# PSU_VCC1V5_Buck.net
KiCad netlist of a schematic drawn in Altium Designer
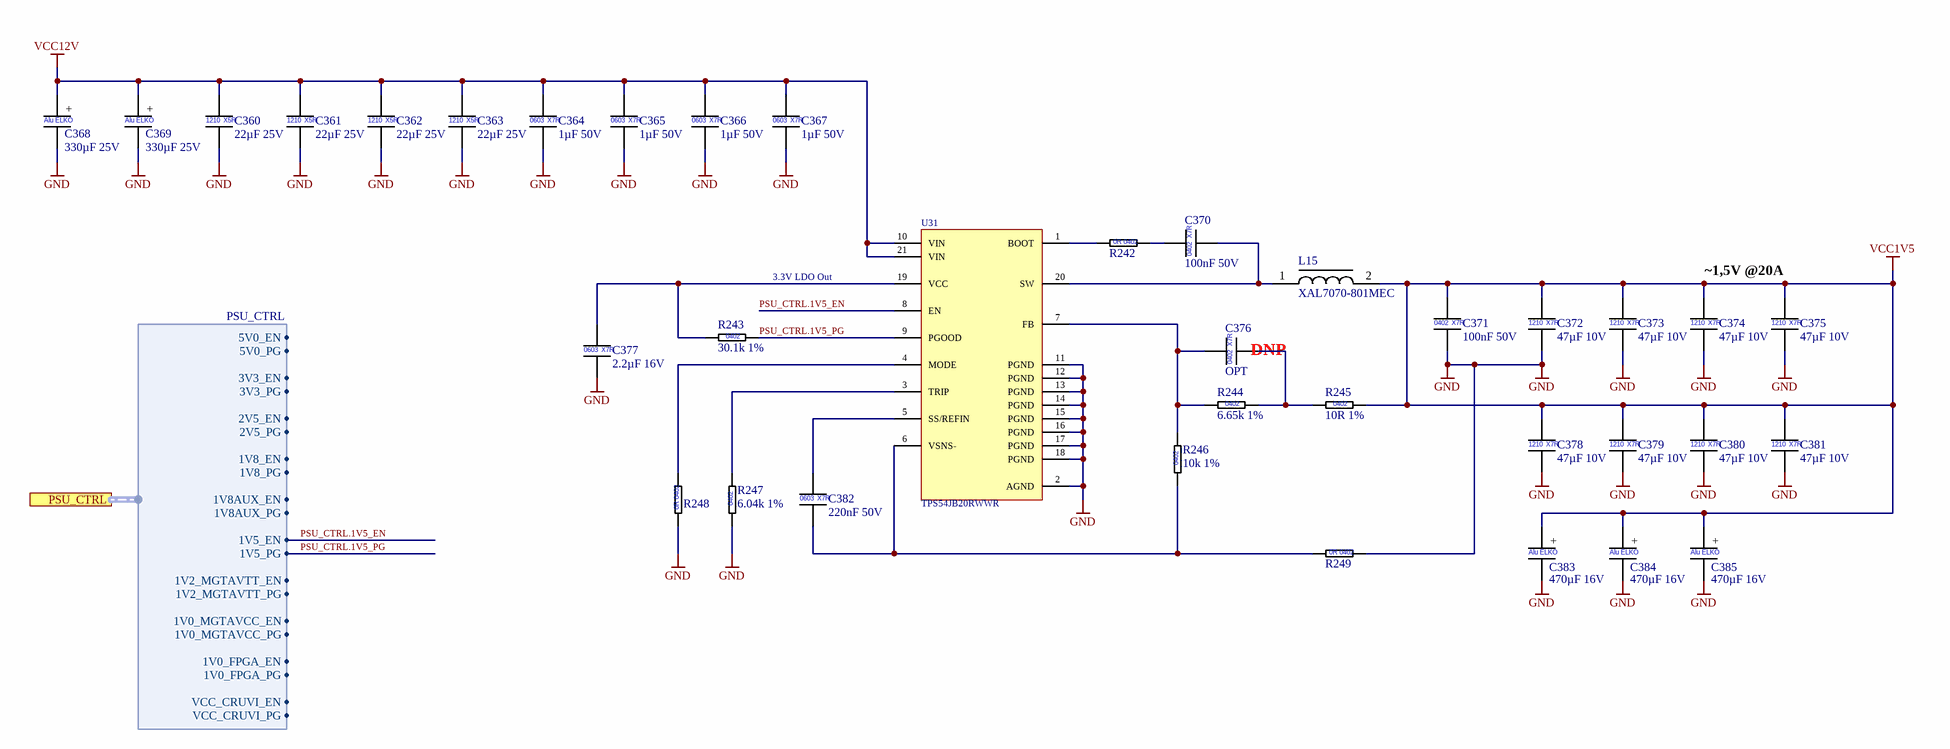
[diagram p0: PSU_VCC1V5_Buck.SchDoc]

(export (version "E")
  (design (tool "Eeschema 10.0.6"))
  (components
    (comp (ref "C360")
      (value "22µF 25V")
      (footprint "Cap:CAP_1210")
      (description "Multilayer Ceramic Capacitors MLCC - SMD/SMT 1210 25VDC")
      (libsource (lib "Cap") (part "CAP_1210_22µF_25V"))
    )
    (comp (ref "C361")
      (value "22µF 25V")
      (footprint "Cap:CAP_1210")
      (description "Multilayer Ceramic Capacitors MLCC - SMD/SMT 1210 25VDC")
      (libsource (lib "Cap") (part "CAP_1210_22µF_25V"))
    )
    (comp (ref "C362")
      (value "22µF 25V")
      (footprint "Cap:CAP_1210")
      (description "Multilayer Ceramic Capacitors MLCC - SMD/SMT 1210 25VDC")
      (libsource (lib "Cap") (part "CAP_1210_22µF_25V"))
    )
    (comp (ref "C363")
      (value "22µF 25V")
      (footprint "Cap:CAP_1210")
      (description "Multilayer Ceramic Capacitors MLCC - SMD/SMT 1210 25VDC")
      (libsource (lib "Cap") (part "CAP_1210_22µF_25V"))
    )
    (comp (ref "C364")
      (value "1µF 50V")
      (footprint "CAP_0603")
      (description "Multilayer Ceramic Capacitors MLCC - SMD/SMT 50V 1uF X7R 0603 10%")
      (libsource (lib "Cap") (part "CAP_0603_1µF_50V_X7R_10%"))
    )
    (comp (ref "C365")
      (value "1µF 50V")
      (footprint "CAP_0603")
      (description "Multilayer Ceramic Capacitors MLCC - SMD/SMT 50V 1uF X7R 0603 10%")
      (libsource (lib "Cap") (part "CAP_0603_1µF_50V_X7R_10%"))
    )
    (comp (ref "C366")
      (value "1µF 50V")
      (footprint "CAP_0603")
      (description "Multilayer Ceramic Capacitors MLCC - SMD/SMT 50V 1uF X7R 0603 10%")
      (libsource (lib "Cap") (part "CAP_0603_1µF_50V_X7R_10%"))
    )
    (comp (ref "C367")
      (value "1µF 50V")
      (footprint "CAP_0603")
      (description "Multilayer Ceramic Capacitors MLCC - SMD/SMT 50V 1uF X7R 0603 10%")
      (libsource (lib "Cap") (part "CAP_0603_1µF_50V_X7R_10%"))
    )
    (comp (ref "C368")
      (value "330µF 25V")
      (footprint "Cap:WCAP-PTG5_D10H12.5")
      (description "Organische Polymer-Aluminiumkondensatoren 330uF 25 Volts 20% AEC-Q200")
      (libsource (lib "Cap") (part "CAP_D10L12.5_330µF_25V"))
    )
    (comp (ref "C369")
      (value "330µF 25V")
      (footprint "Cap:WCAP-PTG5_D10H12.5")
      (description "Organische Polymer-Aluminiumkondensatoren 330uF 25 Volts 20% AEC-Q200")
      (libsource (lib "Cap") (part "CAP_D10L12.5_330µF_25V"))
    )
    (comp (ref "C370")
      (value "100nF 50V")
      (footprint "Cap:CAP_0402")
      (description "Multilayer Ceramic Capacitors MLCC - SMD/SMT 0402 50VDC")
      (libsource (lib "") (part "CAP_0402_100nF_50V_1"))
    )
    (comp (ref "C371")
      (value "100nF 50V")
      (footprint "Cap:CAP_0402")
      (description "Multilayer Ceramic Capacitors MLCC - SMD/SMT 0402 50VDC")
      (libsource (lib "Cap") (part "CAP_0402_100nF_50V"))
    )
    (comp (ref "C372")
      (value "47µF 10V")
      (footprint "Cap:CAP_1210")
      (description "Multilayer Ceramic Capacitors MLCC - SMD/SMT 47 uF 10 VDC 10% 1210 X7R")
      (libsource (lib "Cap") (part "CAP_1210_47µF_10V_X7R_10%"))
    )
    (comp (ref "C373")
      (value "47µF 10V")
      (footprint "Cap:CAP_1210")
      (description "Multilayer Ceramic Capacitors MLCC - SMD/SMT 47 uF 10 VDC 10% 1210 X7R")
      (libsource (lib "Cap") (part "CAP_1210_47µF_10V_X7R_10%"))
    )
    (comp (ref "C374")
      (value "47µF 10V")
      (footprint "Cap:CAP_1210")
      (description "Multilayer Ceramic Capacitors MLCC - SMD/SMT 47 uF 10 VDC 10% 1210 X7R")
      (libsource (lib "Cap") (part "CAP_1210_47µF_10V_X7R_10%"))
    )
    (comp (ref "C375")
      (value "47µF 10V")
      (footprint "Cap:CAP_1210")
      (description "Multilayer Ceramic Capacitors MLCC - SMD/SMT 47 uF 10 VDC 10% 1210 X7R")
      (libsource (lib "Cap") (part "CAP_1210_47µF_10V_X7R_10%"))
    )
    (comp (ref "C376")
      (value "OPT")
      (footprint "Cap:CAP_0402")
      (description "Multilayer Ceramic Capacitors MLCC - SMD/SMT 0402 Optional Placeholder")
      (libsource (lib "Cap") (part "CAP_0402_OPT"))
    )
    (comp (ref "C377")
      (value "2.2µF 16V")
      (footprint "Cap:CAP_0603")
      (description "Multilayer Ceramic Capacitors MLCC - SMD/SMT 2.2 uF 16 VDC 10% 0603 X7R")
      (libsource (lib "Cap") (part "CAP_0603_2.2µF_16V_X7R_10%"))
    )
    (comp (ref "C378")
      (value "47µF 10V")
      (footprint "Cap:CAP_1210")
      (description "Multilayer Ceramic Capacitors MLCC - SMD/SMT 47 uF 10 VDC 10% 1210 X7R")
      (libsource (lib "Cap") (part "CAP_1210_47µF_10V_X7R_10%"))
    )
    (comp (ref "C379")
      (value "47µF 10V")
      (footprint "Cap:CAP_1210")
      (description "Multilayer Ceramic Capacitors MLCC - SMD/SMT 47 uF 10 VDC 10% 1210 X7R")
      (libsource (lib "Cap") (part "CAP_1210_47µF_10V_X7R_10%"))
    )
    (comp (ref "C380")
      (value "47µF 10V")
      (footprint "Cap:CAP_1210")
      (description "Multilayer Ceramic Capacitors MLCC - SMD/SMT 47 uF 10 VDC 10% 1210 X7R")
      (libsource (lib "Cap") (part "CAP_1210_47µF_10V_X7R_10%"))
    )
    (comp (ref "C381")
      (value "47µF 10V")
      (footprint "Cap:CAP_1210")
      (description "Multilayer Ceramic Capacitors MLCC - SMD/SMT 47 uF 10 VDC 10% 1210 X7R")
      (libsource (lib "Cap") (part "CAP_1210_47µF_10V_X7R_10%"))
    )
    (comp (ref "C382")
      (value "220nF 50V")
      (footprint "CAP_0603")
      (description "Multilayer Ceramic Capacitors MLCC - SMD/SMT 0.22 uF 50 VDC 10% 0603 X7R")
      (libsource (lib "Cap") (part "CAP_0603_220nF_50V_X7R_10%"))
    )
    (comp (ref "C383")
      (value "470µF 16V")
      (footprint "Cap:WCAP-PTG5_D8H13")
      (description "Organische Polymer-Aluminiumkondensatoren 470uF 16 Volts 20%")
      (libsource (lib "Cap") (part "CAP_D8L9_470µF_16V"))
    )
    (comp (ref "C384")
      (value "470µF 16V")
      (footprint "Cap:WCAP-PTG5_D8H13")
      (description "Organische Polymer-Aluminiumkondensatoren 470uF 16 Volts 20%")
      (libsource (lib "Cap") (part "CAP_D8L9_470µF_16V"))
    )
    (comp (ref "C385")
      (value "470µF 16V")
      (footprint "Cap:WCAP-PTG5_D8H13")
      (description "Organische Polymer-Aluminiumkondensatoren 470uF 16 Volts 20%")
      (libsource (lib "Cap") (part "CAP_D8L9_470µF_16V"))
    )
    (comp (ref "L15")
      (value "XAL7070-801MEC")
      (footprint "indc:COILCRAFT_XAL7070")
      (description "Power Inductors - SMD 800nH Shld 20% 25.8A 2.29mOhms AECQ200")
      (libsource (lib "Indc") (part "XAL7070-801MEC_Power Inductors SMD 800nH Shld 20% 25.8A 2.29mOhms AECQ200"))
    )
    (comp (ref "R242")
      (value "0R Jumper")
      (footprint "res:RES_0402")
      (description "Thick Film Resistors - SMD 0Ohm")
      (libsource (lib "Res") (part "RES_0402_0R Jumper"))
    )
    (comp (ref "R243")
      (value "30.1k 1%")
      (footprint "res:RES_0402")
      (description "Thick Film Resistors - SMD 30.1kOhm 1%")
      (libsource (lib "Res") (part "RES_0402_30.1k_1%"))
    )
    (comp (ref "R244")
      (value "6.65k 1%")
      (footprint "Res:RES_0402")
      (description "Thick Film Resistors - SMD 6.65kOhm 1%")
      (libsource (lib "Res") (part "RES_0402_6.65k_1%"))
    )
    (comp (ref "R245")
      (value "10R 1%")
      (footprint "res:RES_0402")
      (description "Thick Film Resistors - SMD 10Ohm 1%")
      (libsource (lib "Res") (part "RES_0402_10R_1%"))
    )
    (comp (ref "R246")
      (value "10k 1%")
      (footprint "Res:RES_0402")
      (description "Thick Film Resistors - SMD 10kOhm 1%")
      (libsource (lib "Res") (part "RES_0402_10k_1%"))
    )
    (comp (ref "R247")
      (value "6.04k 1%")
      (footprint "Res:RES_0402")
      (description "Thick Film Resistors - SMD 6.04kOhm 1%")
      (libsource (lib "Res") (part "RES_0402_6.04k_1%"))
    )
    (comp (ref "R248")
      (value "0R Jumper")
      (footprint "res:RES_0402")
      (description "Thick Film Resistors - SMD 0Ohm")
      (libsource (lib "Res") (part "RES_0402_0R Jumper"))
    )
    (comp (ref "R249")
      (value "0R Jumper")
      (footprint "res:RES_0402")
      (description "Thick Film Resistors - SMD 0Ohm")
      (libsource (lib "Res") (part "RES_0402_0R Jumper"))
    )
    (comp (ref "U31")
      (value "TPS54JB20RWWR")
      (footprint "power:VQFN-HR21_RWW0021A")
      (description "Switching Voltage Regulators 2.7-V to 16-V input 20-A synchronous Buck")
      (libsource (lib "Power") (part "TPS54JB20RWWR_Switching Voltage Regulators 2.7-V to 16-V input 20-A synchronous Buck"))
    )
  )
  (nets
    (net (code "2") (name "/PSU_CTRL.1V5_EN") (class "Default")
      (node (ref "U31") (pin "8") (pinfunction "EN_8") (pintype "passive"))
    )
    (net (code "3") (name "/PSU_CTRL.1V5_PG") (class "Default")
      (node (ref "R243") (pin "2") (pinfunction "2_2") (pintype "passive"))
      (node (ref "U31") (pin "9") (pinfunction "PGOOD_9") (pintype "passive"))
    )
    (net (code "5") (name "GND") (class "Default")
      (node (ref "C360") (pin "2") (pinfunction "2_2") (pintype "passive"))
      (node (ref "C361") (pin "2") (pinfunction "2_2") (pintype "passive"))
      (node (ref "C362") (pin "2") (pinfunction "2_2") (pintype "passive"))
      (node (ref "C363") (pin "2") (pinfunction "2_2") (pintype "passive"))
      (node (ref "C364") (pin "2") (pinfunction "2_2") (pintype "passive"))
      (node (ref "C365") (pin "2") (pinfunction "2_2") (pintype "passive"))
      (node (ref "C366") (pin "2") (pinfunction "2_2") (pintype "passive"))
      (node (ref "C367") (pin "2") (pinfunction "2_2") (pintype "passive"))
      (node (ref "C368") (pin "2") (pinfunction "2_2") (pintype "passive"))
      (node (ref "C369") (pin "2") (pinfunction "2_2") (pintype "passive"))
      (node (ref "C371") (pin "2") (pinfunction "2_2") (pintype "passive"))
      (node (ref "C372") (pin "2") (pinfunction "2_2") (pintype "passive"))
      (node (ref "C373") (pin "2") (pinfunction "2_2") (pintype "passive"))
      (node (ref "C374") (pin "2") (pinfunction "2_2") (pintype "passive"))
      (node (ref "C375") (pin "2") (pinfunction "2_2") (pintype "passive"))
      (node (ref "C377") (pin "2") (pinfunction "2_2") (pintype "passive"))
      (node (ref "C378") (pin "2") (pinfunction "2_2") (pintype "passive"))
      (node (ref "C379") (pin "2") (pinfunction "2_2") (pintype "passive"))
      (node (ref "C380") (pin "2") (pinfunction "2_2") (pintype "passive"))
      (node (ref "C381") (pin "2") (pinfunction "2_2") (pintype "passive"))
      (node (ref "C383") (pin "2") (pinfunction "2_2") (pintype "passive"))
      (node (ref "C384") (pin "2") (pinfunction "2_2") (pintype "passive"))
      (node (ref "C385") (pin "2") (pinfunction "2_2") (pintype "passive"))
      (node (ref "R247") (pin "1") (pinfunction "1_1") (pintype "passive"))
      (node (ref "R248") (pin "1") (pinfunction "1_1") (pintype "passive"))
      (node (ref "R249") (pin "2") (pinfunction "2_2") (pintype "passive"))
      (node (ref "U31") (pin "11") (pinfunction "PGND_11") (pintype "passive"))
      (node (ref "U31") (pin "12") (pinfunction "PGND_12") (pintype "passive"))
      (node (ref "U31") (pin "13") (pinfunction "PGND_13") (pintype "passive"))
      (node (ref "U31") (pin "14") (pinfunction "PGND_14") (pintype "passive"))
      (node (ref "U31") (pin "15") (pinfunction "PGND_15") (pintype "passive"))
      (node (ref "U31") (pin "16") (pinfunction "PGND_16") (pintype "passive"))
      (node (ref "U31") (pin "17") (pinfunction "PGND_17") (pintype "passive"))
      (node (ref "U31") (pin "18") (pinfunction "PGND_18") (pintype "passive"))
      (node (ref "U31") (pin "2") (pinfunction "AGND_2") (pintype "passive"))
    )
    (net (code "6") (name "Net-(C370-Pad1)") (class "Default")
      (node (ref "C370") (pin "1") (pinfunction "1_1") (pintype "passive"))
      (node (ref "R242") (pin "2") (pinfunction "2_2") (pintype "passive"))
    )
    (net (code "7") (name "Net-(C376-Pad2)") (class "Default")
      (node (ref "C376") (pin "2") (pinfunction "2_2") (pintype "passive"))
      (node (ref "R244") (pin "2") (pinfunction "2_2") (pintype "passive"))
      (node (ref "R245") (pin "1") (pinfunction "1_1") (pintype "passive"))
    )
    (net (code "8") (name "Net-(U31-BOOT)") (class "Default")
      (node (ref "R242") (pin "1") (pinfunction "1_1") (pintype "passive"))
      (node (ref "U31") (pin "1") (pinfunction "BOOT_1") (pintype "passive"))
    )
    (net (code "9") (name "Net-(U31-FB)") (class "Default")
      (node (ref "C376") (pin "1") (pinfunction "1_1") (pintype "passive"))
      (node (ref "R244") (pin "1") (pinfunction "1_1") (pintype "passive"))
      (node (ref "R246") (pin "2") (pinfunction "2_2") (pintype "passive"))
      (node (ref "U31") (pin "7") (pinfunction "FB_7") (pintype "passive"))
    )
    (net (code "10") (name "Net-(U31-MODE)") (class "Default")
      (node (ref "R248") (pin "2") (pinfunction "2_2") (pintype "passive"))
      (node (ref "U31") (pin "4") (pinfunction "MODE_4") (pintype "passive"))
    )
    (net (code "11") (name "Net-(U31-SS{slash}REFIN)") (class "Default")
      (node (ref "C382") (pin "1") (pinfunction "1_1") (pintype "passive"))
      (node (ref "U31") (pin "5") (pinfunction "SS/REFIN_5") (pintype "passive"))
    )
    (net (code "12") (name "Net-(U31-SW)") (class "Default")
      (node (ref "C370") (pin "2") (pinfunction "2_2") (pintype "passive"))
      (node (ref "L15") (pin "1") (pinfunction "1_1") (pintype "passive"))
      (node (ref "U31") (pin "20") (pinfunction "SW_20") (pintype "passive"))
    )
    (net (code "13") (name "Net-(U31-TRIP)") (class "Default")
      (node (ref "R247") (pin "2") (pinfunction "2_2") (pintype "passive"))
      (node (ref "U31") (pin "3") (pinfunction "TRIP_3") (pintype "passive"))
    )
    (net (code "14") (name "Net-(U31-VCC)") (class "Default")
      (node (ref "C377") (pin "1") (pinfunction "1_1") (pintype "passive"))
      (node (ref "R243") (pin "1") (pinfunction "1_1") (pintype "passive"))
      (node (ref "U31") (pin "19") (pinfunction "VCC_19") (pintype "passive"))
    )
    (net (code "15") (name "Net-(U31-VSNS-)") (class "Default")
      (node (ref "C382") (pin "2") (pinfunction "2_2") (pintype "passive"))
      (node (ref "R246") (pin "1") (pinfunction "1_1") (pintype "passive"))
      (node (ref "R249") (pin "1") (pinfunction "1_1") (pintype "passive"))
      (node (ref "U31") (pin "6") (pinfunction "VSNS-_6") (pintype "passive"))
    )
    (net (code "16") (name "VCC1V5") (class "Default")
      (node (ref "C371") (pin "1") (pinfunction "1_1") (pintype "passive"))
      (node (ref "C372") (pin "1") (pinfunction "1_1") (pintype "passive"))
      (node (ref "C373") (pin "1") (pinfunction "1_1") (pintype "passive"))
      (node (ref "C374") (pin "1") (pinfunction "1_1") (pintype "passive"))
      (node (ref "C375") (pin "1") (pinfunction "1_1") (pintype "passive"))
      (node (ref "C378") (pin "1") (pinfunction "1_1") (pintype "passive"))
      (node (ref "C379") (pin "1") (pinfunction "1_1") (pintype "passive"))
      (node (ref "C380") (pin "1") (pinfunction "1_1") (pintype "passive"))
      (node (ref "C381") (pin "1") (pinfunction "1_1") (pintype "passive"))
      (node (ref "C383") (pin "1") (pinfunction "1_1") (pintype "passive"))
      (node (ref "C384") (pin "1") (pinfunction "1_1") (pintype "passive"))
      (node (ref "C385") (pin "1") (pinfunction "1_1") (pintype "passive"))
      (node (ref "L15") (pin "2") (pinfunction "2_2") (pintype "passive"))
      (node (ref "R245") (pin "2") (pinfunction "2_2") (pintype "passive"))
    )
    (net (code "17") (name "VCC12V") (class "Default")
      (node (ref "C360") (pin "1") (pinfunction "1_1") (pintype "passive"))
      (node (ref "C361") (pin "1") (pinfunction "1_1") (pintype "passive"))
      (node (ref "C362") (pin "1") (pinfunction "1_1") (pintype "passive"))
      (node (ref "C363") (pin "1") (pinfunction "1_1") (pintype "passive"))
      (node (ref "C364") (pin "1") (pinfunction "1_1") (pintype "passive"))
      (node (ref "C365") (pin "1") (pinfunction "1_1") (pintype "passive"))
      (node (ref "C366") (pin "1") (pinfunction "1_1") (pintype "passive"))
      (node (ref "C367") (pin "1") (pinfunction "1_1") (pintype "passive"))
      (node (ref "C368") (pin "1") (pinfunction "1_1") (pintype "passive"))
      (node (ref "C369") (pin "1") (pinfunction "1_1") (pintype "passive"))
      (node (ref "U31") (pin "10") (pinfunction "VIN_10") (pintype "passive"))
      (node (ref "U31") (pin "21") (pinfunction "VIN_21") (pintype "passive"))
    )
  )
)
